# board.net
KiCad netlist of a schematic drawn in EAGLE
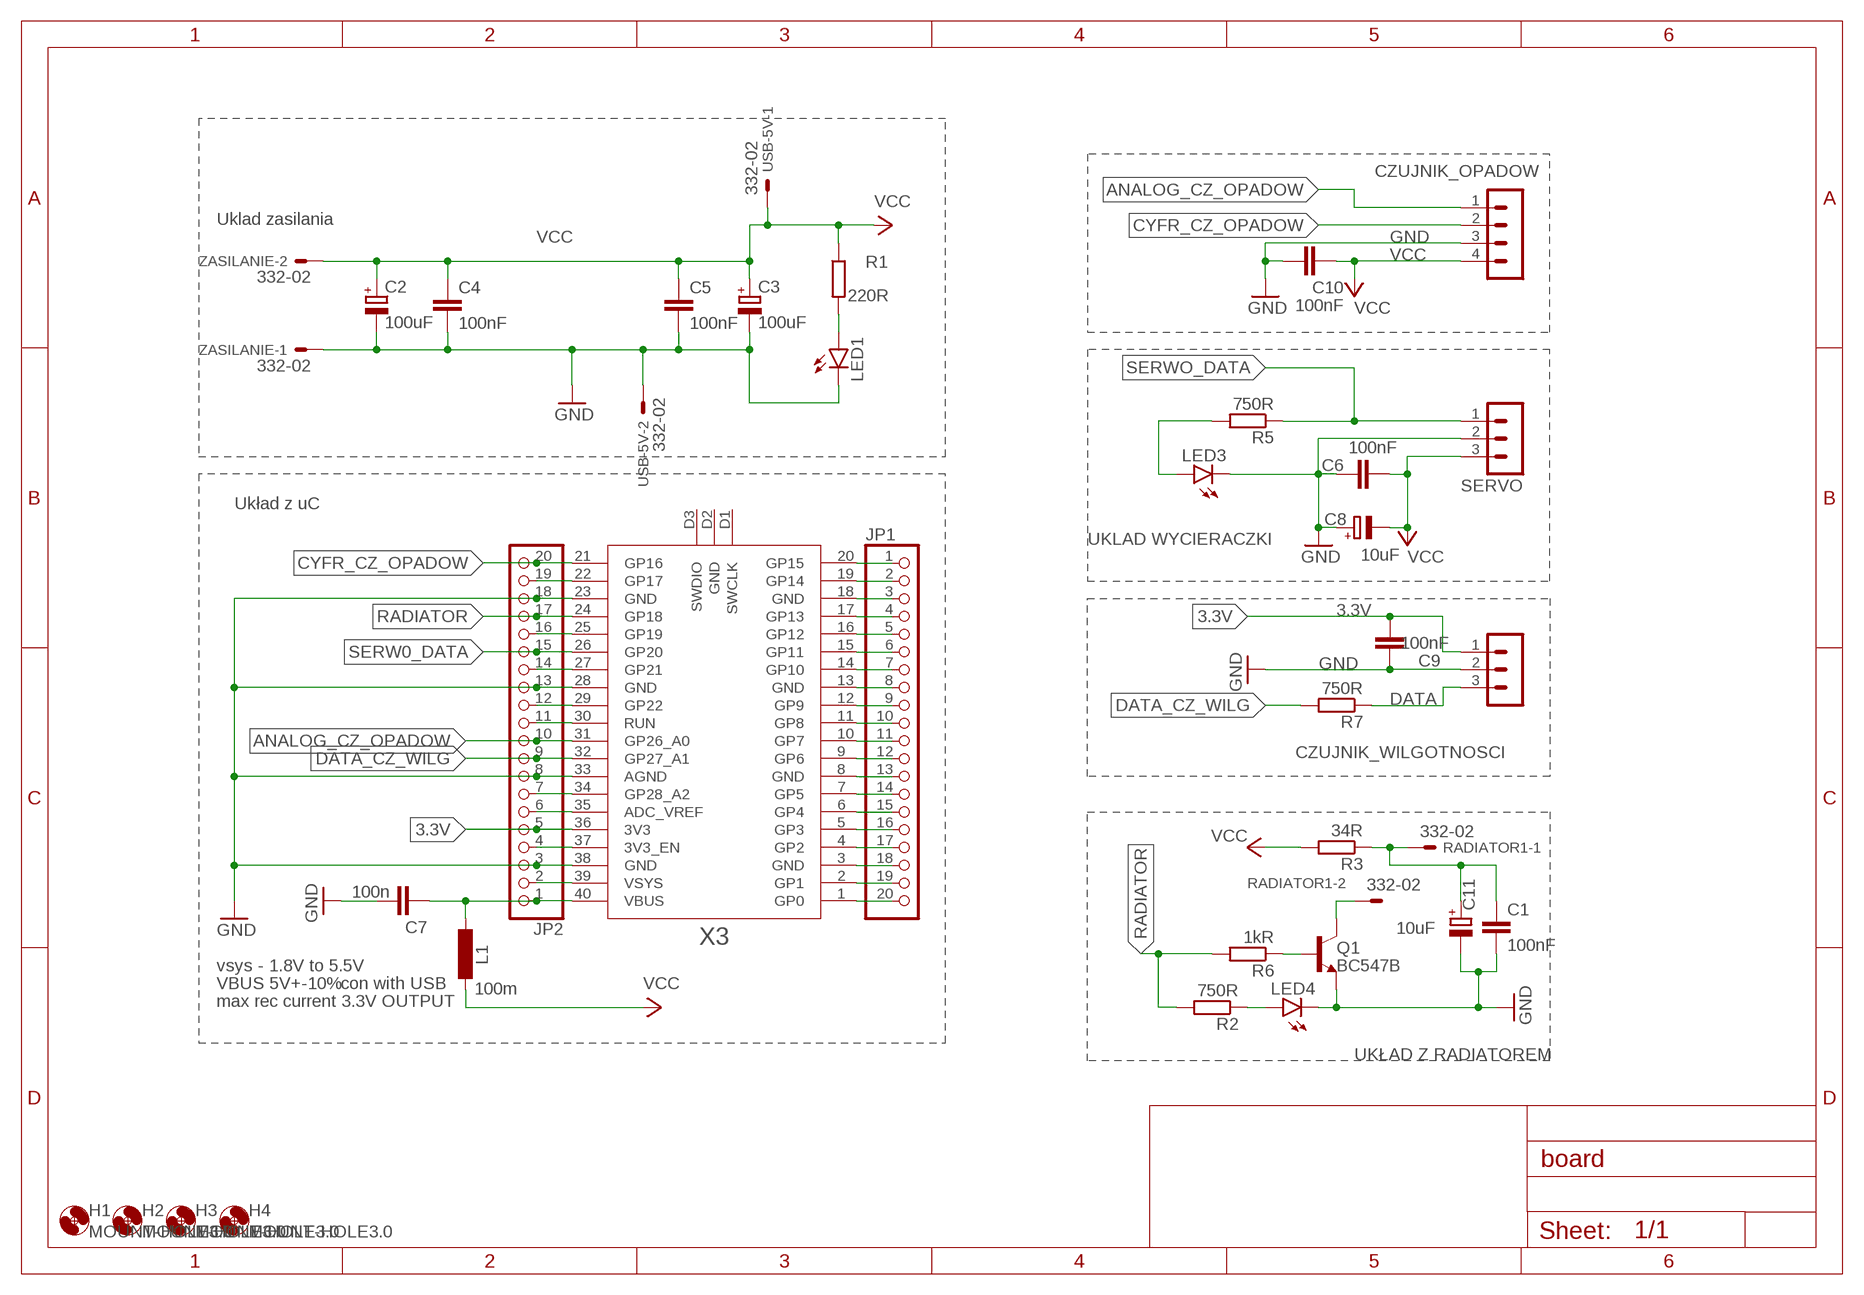
[diagram p0: schematic, sheet 1]

(export (version "E")
  (design (tool "Eeschema 10.0.6"))
  (components
    (comp (ref "C1")
      (value "100nF")
      (footprint "eagle-import:C0805")
      (libsource (lib "eagle-import") (part "C-EUC0805"))
    )
    (comp (ref "C2")
      (value "100uF")
      (footprint "eagle-import:UD-5X5,8_NICHICON")
      (libsource (lib "eagle-import") (part "CPOL-EUUD-5X5,8"))
    )
    (comp (ref "C3")
      (value "100uF")
      (footprint "eagle-import:UD-5X5,8_NICHICON")
      (libsource (lib "eagle-import") (part "CPOL-EUUD-5X5,8"))
    )
    (comp (ref "C4")
      (value "100nF")
      (footprint "eagle-import:C0805")
      (libsource (lib "eagle-import") (part "C-EUC0805"))
    )
    (comp (ref "C5")
      (value "100nF")
      (footprint "eagle-import:C0805")
      (libsource (lib "eagle-import") (part "C-EUC0805"))
    )
    (comp (ref "C6")
      (value "100nF")
      (footprint "eagle-import:C0805")
      (libsource (lib "eagle-import") (part "C-EUC0805"))
    )
    (comp (ref "C7")
      (value "100n")
      (footprint "eagle-import:C0603")
      (libsource (lib "eagle-import") (part "C-EUC0603"))
    )
    (comp (ref "C8")
      (value "10uF")
      (footprint "eagle-import:E5-8,5")
      (libsource (lib "eagle-import") (part "CPOL-EUE5-8.5"))
    )
    (comp (ref "C9")
      (value "100nF")
      (footprint "eagle-import:C0805")
      (libsource (lib "eagle-import") (part "C-EUC0805"))
    )
    (comp (ref "C10")
      (value "100nF")
      (footprint "eagle-import:C0805")
      (libsource (lib "eagle-import") (part "C-EUC0805"))
    )
    (comp (ref "C11")
      (value "10uF")
      (footprint "eagle-import:E5-8,5")
      (libsource (lib "eagle-import") (part "CPOL-EUE5-8.5"))
    )
    (comp (ref "CZUJNIK_OPADOW")
      (value "MA04-1")
      (footprint "eagle-import:MA04-1")
      (libsource (lib "eagle-import") (part "MA04-1"))
    )
    (comp (ref "CZUJNIK_WILGOTNOSCI")
      (value "MA03-1")
      (footprint "eagle-import:MA03-1")
      (libsource (lib "eagle-import") (part "MA03-1"))
    )
    (comp (ref "H1")
      (value "MOUNT-HOLE3.0")
      (footprint "eagle-import:3,0")
      (libsource (lib "eagle-import") (part "MOUNT-HOLE3.0"))
    )
    (comp (ref "H2")
      (value "MOUNT-HOLE3.0")
      (footprint "eagle-import:3,0")
      (libsource (lib "eagle-import") (part "MOUNT-HOLE3.0"))
    )
    (comp (ref "H3")
      (value "MOUNT-HOLE3.0")
      (footprint "eagle-import:3,0")
      (libsource (lib "eagle-import") (part "MOUNT-HOLE3.0"))
    )
    (comp (ref "H4")
      (value "MOUNT-HOLE3.0")
      (footprint "eagle-import:3,0")
      (libsource (lib "eagle-import") (part "MOUNT-HOLE3.0"))
    )
    (comp (ref "JP1")
      (value "PINHD-1X20")
      (footprint "eagle-import:1X20")
      (libsource (lib "eagle-import") (part "PINHD-1X20"))
    )
    (comp (ref "JP2")
      (value "PINHD-1X20")
      (footprint "eagle-import:1X20")
      (libsource (lib "eagle-import") (part "PINHD-1X20"))
    )
    (comp (ref "L1")
      (value "100m")
      (footprint "eagle-import:L2012C")
      (libsource (lib "eagle-import") (part "L-EUL2012C"))
    )
    (comp (ref "LED1")
      (value "LEDSML0805")
      (footprint "eagle-import:SML0805")
      (libsource (lib "eagle-import") (part "LEDSML0805"))
    )
    (comp (ref "LED3")
      (value "LEDSML0805")
      (footprint "eagle-import:SML0805")
      (libsource (lib "eagle-import") (part "LEDSML0805"))
    )
    (comp (ref "LED4")
      (value "LEDSML0805")
      (footprint "eagle-import:SML0805")
      (libsource (lib "eagle-import") (part "LEDSML0805"))
    )
    (comp (ref "Q1")
      (value "BC547B")
      (footprint "eagle-import:TO92")
      (libsource (lib "eagle-import") (part "BC547B"))
    )
    (comp (ref "R1")
      (value "220R")
      (footprint "eagle-import:R0805")
      (libsource (lib "eagle-import") (part "R-EU_R0805"))
    )
    (comp (ref "R2")
      (value "750R")
      (footprint "eagle-import:R0805")
      (libsource (lib "eagle-import") (part "R-EU_R0805"))
    )
    (comp (ref "R3")
      (value "34R")
      (footprint "eagle-import:R0805")
      (libsource (lib "eagle-import") (part "R-EU_R0805"))
    )
    (comp (ref "R5")
      (value "750R")
      (footprint "eagle-import:R0805")
      (libsource (lib "eagle-import") (part "R-EU_R0805"))
    )
    (comp (ref "R6")
      (value "1kR")
      (footprint "eagle-import:R0805")
      (libsource (lib "eagle-import") (part "R-EU_R0805"))
    )
    (comp (ref "R7")
      (value "750R")
      (footprint "eagle-import:R0805")
      (libsource (lib "eagle-import") (part "R-EU_R0805"))
    )
    (comp (ref "RADIATOR1")
      (value "332-02")
      (footprint "eagle-import:332-02")
      (libsource (lib "eagle-import") (part "332-02"))
    )
    (comp (ref "SERVO")
      (value "MA03-1")
      (footprint "eagle-import:MA03-1")
      (libsource (lib "eagle-import") (part "MA03-1"))
    )
    (comp (ref "USB-5V")
      (value "332-02")
      (footprint "eagle-import:332-02")
      (libsource (lib "eagle-import") (part "332-02"))
    )
    (comp (ref "X3")
      (value "RPI_PICO_IG-TH")
      (footprint "eagle-import:RPI_PICO_TH")
      (libsource (lib "eagle-import") (part "RPI_PICO_IG-TH"))
    )
    (comp (ref "ZASILANIE")
      (value "332-02")
      (footprint "eagle-import:332-02")
      (libsource (lib "eagle-import") (part "332-02"))
    )
  )
  (nets
    (net (code "1") (name "/DATA") (class "Default")
      (node (ref "CZUJNIK_WILGOTNOSCI") (pin "3") (pinfunction "3_3") (pintype "passive"))
      (node (ref "R7") (pin "1") (pinfunction "1_1") (pintype "passive"))
    )
    (net (code "2") (name "3.3V") (class "Default")
      (node (ref "C9") (pin "2") (pinfunction "2_2") (pintype "passive"))
      (node (ref "CZUJNIK_WILGOTNOSCI") (pin "1") (pinfunction "1_1") (pintype "passive"))
      (node (ref "JP2") (pin "5") (pinfunction "5_5") (pintype "passive"))
      (node (ref "X3") (pin "36") (pinfunction "3V3_36") (pintype "bidirectional"))
    )
    (net (code "3") (name "ANALOG_CZ_OPADOW") (class "Default")
      (node (ref "CZUJNIK_OPADOW") (pin "1") (pinfunction "1_1") (pintype "passive"))
      (node (ref "JP2") (pin "10") (pinfunction "10_10") (pintype "passive"))
      (node (ref "X3") (pin "31") (pinfunction "GP26_A0_31") (pintype "bidirectional"))
    )
    (net (code "4") (name "CYFR_CZ_OPADOW") (class "Default")
      (node (ref "CZUJNIK_OPADOW") (pin "2") (pinfunction "2_2") (pintype "passive"))
      (node (ref "JP2") (pin "20") (pinfunction "20_20") (pintype "passive"))
      (node (ref "X3") (pin "21") (pinfunction "GP16_21") (pintype "bidirectional"))
    )
    (net (code "5") (name "DATA_CZ_WILG") (class "Default")
      (node (ref "JP2") (pin "9") (pinfunction "9_9") (pintype "passive"))
      (node (ref "R7") (pin "2") (pinfunction "2_2") (pintype "passive"))
      (node (ref "X3") (pin "32") (pinfunction "GP27_A1_32") (pintype "bidirectional"))
    )
    (net (code "6") (name "GND") (class "Default")
      (node (ref "C1") (pin "2") (pinfunction "2_2") (pintype "passive"))
      (node (ref "C10") (pin "2") (pinfunction "2_2") (pintype "passive"))
      (node (ref "C11") (pin "-") (pinfunction "-_-") (pintype "passive"))
      (node (ref "C2") (pin "-") (pinfunction "-_-") (pintype "passive"))
      (node (ref "C3") (pin "-") (pinfunction "-_-") (pintype "passive"))
      (node (ref "C4") (pin "2") (pinfunction "2_2") (pintype "passive"))
      (node (ref "C5") (pin "2") (pinfunction "2_2") (pintype "passive"))
      (node (ref "C6") (pin "1") (pinfunction "1_1") (pintype "passive"))
      (node (ref "C7") (pin "2") (pinfunction "2_2") (pintype "passive"))
      (node (ref "C8") (pin "+") (pinfunction "+_+") (pintype "passive"))
      (node (ref "C9") (pin "1") (pinfunction "1_1") (pintype "passive"))
      (node (ref "CZUJNIK_OPADOW") (pin "3") (pinfunction "3_3") (pintype "passive"))
      (node (ref "CZUJNIK_WILGOTNOSCI") (pin "2") (pinfunction "2_2") (pintype "passive"))
      (node (ref "JP2") (pin "13") (pinfunction "13_13") (pintype "passive"))
      (node (ref "JP2") (pin "18") (pinfunction "18_18") (pintype "passive"))
      (node (ref "JP2") (pin "3") (pinfunction "3_3") (pintype "passive"))
      (node (ref "JP2") (pin "8") (pinfunction "8_8") (pintype "passive"))
      (node (ref "LED1") (pin "C") (pinfunction "C_C") (pintype "passive"))
      (node (ref "LED3") (pin "C") (pinfunction "C_C") (pintype "passive"))
      (node (ref "LED4") (pin "C") (pinfunction "C_C") (pintype "passive"))
      (node (ref "Q1") (pin "1") (pinfunction "E_1") (pintype "passive"))
      (node (ref "SERVO") (pin "2") (pinfunction "2_2") (pintype "passive"))
      (node (ref "USB-5V") (pin "2") (pinfunction "S_2") (pintype "passive"))
      (node (ref "X3") (pin "23") (pinfunction "GND_23") (pintype "bidirectional"))
      (node (ref "X3") (pin "28") (pinfunction "GND_28") (pintype "bidirectional"))
      (node (ref "X3") (pin "33") (pinfunction "AGND_33") (pintype "bidirectional"))
      (node (ref "X3") (pin "38") (pinfunction "GND_38") (pintype "bidirectional"))
      (node (ref "ZASILANIE") (pin "1") (pinfunction "S_1") (pintype "passive"))
    )
    (net (code "7") (name "Net-(JP1-Pad3)") (class "Default")
      (node (ref "JP1") (pin "3") (pinfunction "3_3") (pintype "passive"))
      (node (ref "X3") (pin "18") (pinfunction "GND_18") (pintype "bidirectional"))
    )
    (net (code "8") (name "Net-(JP1-Pad8)") (class "Default")
      (node (ref "JP1") (pin "8") (pinfunction "8_8") (pintype "passive"))
      (node (ref "X3") (pin "13") (pinfunction "GND_13") (pintype "bidirectional"))
    )
    (net (code "9") (name "Net-(JP1-Pad13)") (class "Default")
      (node (ref "JP1") (pin "13") (pinfunction "13_13") (pintype "passive"))
      (node (ref "X3") (pin "8") (pinfunction "GND_8") (pintype "bidirectional"))
    )
    (net (code "10") (name "Net-(JP1-Pad18)") (class "Default")
      (node (ref "JP1") (pin "18") (pinfunction "18_18") (pintype "passive"))
      (node (ref "X3") (pin "3") (pinfunction "GND_3") (pintype "bidirectional"))
    )
    (net (code "11") (name "Net-(LED1-PadA)") (class "Default")
      (node (ref "LED1") (pin "A") (pinfunction "A_A") (pintype "passive"))
      (node (ref "R1") (pin "2") (pinfunction "2_2") (pintype "passive"))
    )
    (net (code "12") (name "Net-(LED3-PadA)") (class "Default")
      (node (ref "LED3") (pin "A") (pinfunction "A_A") (pintype "passive"))
      (node (ref "R5") (pin "2") (pinfunction "2_2") (pintype "passive"))
    )
    (net (code "13") (name "Net-(LED4-PadA)") (class "Default")
      (node (ref "LED4") (pin "A") (pinfunction "A_A") (pintype "passive"))
      (node (ref "R2") (pin "1") (pinfunction "1_1") (pintype "passive"))
    )
    (net (code "14") (name "Net-(Q1-B)") (class "Default")
      (node (ref "Q1") (pin "2") (pinfunction "B_2") (pintype "passive"))
      (node (ref "R6") (pin "1") (pinfunction "1_1") (pintype "passive"))
    )
    (net (code "15") (name "Net-(Q1-C)") (class "Default")
      (node (ref "Q1") (pin "3") (pinfunction "C_3") (pintype "passive"))
      (node (ref "RADIATOR1") (pin "2") (pinfunction "S_2") (pintype "passive"))
    )
    (net (code "16") (name "Net-(RADIATOR1A-S)") (class "Default")
      (node (ref "C1") (pin "1") (pinfunction "1_1") (pintype "passive"))
      (node (ref "C11") (pin "+") (pinfunction "+_+") (pintype "passive"))
      (node (ref "R3") (pin "1") (pinfunction "1_1") (pintype "passive"))
      (node (ref "RADIATOR1") (pin "1") (pinfunction "S_1") (pintype "passive"))
    )
    (net (code "17") (name "Net-(X3-3V3_EN)") (class "Default")
      (node (ref "JP2") (pin "4") (pinfunction "4_4") (pintype "passive"))
      (node (ref "X3") (pin "37") (pinfunction "3V3_EN_37") (pintype "bidirectional"))
    )
    (net (code "18") (name "Net-(X3-ADC_VREF)") (class "Default")
      (node (ref "JP2") (pin "6") (pinfunction "6_6") (pintype "passive"))
      (node (ref "X3") (pin "35") (pinfunction "ADC_VREF_35") (pintype "bidirectional"))
    )
    (net (code "19") (name "Net-(X3-GP0)") (class "Default")
      (node (ref "JP1") (pin "20") (pinfunction "20_20") (pintype "passive"))
      (node (ref "X3") (pin "1") (pinfunction "GP0_1") (pintype "bidirectional"))
    )
    (net (code "20") (name "Net-(X3-GP1)") (class "Default")
      (node (ref "JP1") (pin "19") (pinfunction "19_19") (pintype "passive"))
      (node (ref "X3") (pin "2") (pinfunction "GP1_2") (pintype "bidirectional"))
    )
    (net (code "21") (name "Net-(X3-GP2)") (class "Default")
      (node (ref "JP1") (pin "17") (pinfunction "17_17") (pintype "passive"))
      (node (ref "X3") (pin "4") (pinfunction "GP2_4") (pintype "bidirectional"))
    )
    (net (code "22") (name "Net-(X3-GP3)") (class "Default")
      (node (ref "JP1") (pin "16") (pinfunction "16_16") (pintype "passive"))
      (node (ref "X3") (pin "5") (pinfunction "GP3_5") (pintype "bidirectional"))
    )
    (net (code "23") (name "Net-(X3-GP4)") (class "Default")
      (node (ref "JP1") (pin "15") (pinfunction "15_15") (pintype "passive"))
      (node (ref "X3") (pin "6") (pinfunction "GP4_6") (pintype "bidirectional"))
    )
    (net (code "24") (name "Net-(X3-GP5)") (class "Default")
      (node (ref "JP1") (pin "14") (pinfunction "14_14") (pintype "passive"))
      (node (ref "X3") (pin "7") (pinfunction "GP5_7") (pintype "bidirectional"))
    )
    (net (code "25") (name "Net-(X3-GP6)") (class "Default")
      (node (ref "JP1") (pin "12") (pinfunction "12_12") (pintype "passive"))
      (node (ref "X3") (pin "9") (pinfunction "GP6_9") (pintype "bidirectional"))
    )
    (net (code "26") (name "Net-(X3-GP7)") (class "Default")
      (node (ref "JP1") (pin "11") (pinfunction "11_11") (pintype "passive"))
      (node (ref "X3") (pin "10") (pinfunction "GP7_10") (pintype "bidirectional"))
    )
    (net (code "27") (name "Net-(X3-GP8)") (class "Default")
      (node (ref "JP1") (pin "10") (pinfunction "10_10") (pintype "passive"))
      (node (ref "X3") (pin "11") (pinfunction "GP8_11") (pintype "bidirectional"))
    )
    (net (code "28") (name "Net-(X3-GP9)") (class "Default")
      (node (ref "JP1") (pin "9") (pinfunction "9_9") (pintype "passive"))
      (node (ref "X3") (pin "12") (pinfunction "GP9_12") (pintype "bidirectional"))
    )
    (net (code "29") (name "Net-(X3-GP10)") (class "Default")
      (node (ref "JP1") (pin "7") (pinfunction "7_7") (pintype "passive"))
      (node (ref "X3") (pin "14") (pinfunction "GP10_14") (pintype "bidirectional"))
    )
    (net (code "30") (name "Net-(X3-GP11)") (class "Default")
      (node (ref "JP1") (pin "6") (pinfunction "6_6") (pintype "passive"))
      (node (ref "X3") (pin "15") (pinfunction "GP11_15") (pintype "bidirectional"))
    )
    (net (code "31") (name "Net-(X3-GP12)") (class "Default")
      (node (ref "JP1") (pin "5") (pinfunction "5_5") (pintype "passive"))
      (node (ref "X3") (pin "16") (pinfunction "GP12_16") (pintype "bidirectional"))
    )
    (net (code "32") (name "Net-(X3-GP13)") (class "Default")
      (node (ref "JP1") (pin "4") (pinfunction "4_4") (pintype "passive"))
      (node (ref "X3") (pin "17") (pinfunction "GP13_17") (pintype "bidirectional"))
    )
    (net (code "33") (name "Net-(X3-GP14)") (class "Default")
      (node (ref "JP1") (pin "2") (pinfunction "2_2") (pintype "passive"))
      (node (ref "X3") (pin "19") (pinfunction "GP14_19") (pintype "bidirectional"))
    )
    (net (code "34") (name "Net-(X3-GP15)") (class "Default")
      (node (ref "JP1") (pin "1") (pinfunction "1_1") (pintype "passive"))
      (node (ref "X3") (pin "20") (pinfunction "GP15_20") (pintype "bidirectional"))
    )
    (net (code "35") (name "Net-(X3-GP17)") (class "Default")
      (node (ref "JP2") (pin "19") (pinfunction "19_19") (pintype "passive"))
      (node (ref "X3") (pin "22") (pinfunction "GP17_22") (pintype "bidirectional"))
    )
    (net (code "36") (name "Net-(X3-GP19)") (class "Default")
      (node (ref "JP2") (pin "16") (pinfunction "16_16") (pintype "passive"))
      (node (ref "X3") (pin "25") (pinfunction "GP19_25") (pintype "bidirectional"))
    )
    (net (code "37") (name "Net-(X3-GP21)") (class "Default")
      (node (ref "JP2") (pin "14") (pinfunction "14_14") (pintype "passive"))
      (node (ref "X3") (pin "27") (pinfunction "GP21_27") (pintype "bidirectional"))
    )
    (net (code "38") (name "Net-(X3-GP22)") (class "Default")
      (node (ref "JP2") (pin "12") (pinfunction "12_12") (pintype "passive"))
      (node (ref "X3") (pin "29") (pinfunction "GP22_29") (pintype "bidirectional"))
    )
    (net (code "39") (name "Net-(X3-GP28_A2)") (class "Default")
      (node (ref "JP2") (pin "7") (pinfunction "7_7") (pintype "passive"))
      (node (ref "X3") (pin "34") (pinfunction "GP28_A2_34") (pintype "bidirectional"))
    )
    (net (code "40") (name "Net-(X3-RUN)") (class "Default")
      (node (ref "JP2") (pin "11") (pinfunction "11_11") (pintype "passive"))
      (node (ref "X3") (pin "30") (pinfunction "RUN_30") (pintype "bidirectional"))
    )
    (net (code "41") (name "Net-(X3-VBUS)") (class "Default")
      (node (ref "C7") (pin "1") (pinfunction "1_1") (pintype "passive"))
      (node (ref "JP2") (pin "1") (pinfunction "1_1") (pintype "passive"))
      (node (ref "L1") (pin "2") (pinfunction "2_2") (pintype "passive"))
      (node (ref "X3") (pin "40") (pinfunction "VBUS_40") (pintype "bidirectional"))
    )
    (net (code "42") (name "Net-(X3-VSYS)") (class "Default")
      (node (ref "JP2") (pin "2") (pinfunction "2_2") (pintype "passive"))
      (node (ref "X3") (pin "39") (pinfunction "VSYS_39") (pintype "bidirectional"))
    )
    (net (code "43") (name "RADIATOR") (class "Default")
      (node (ref "JP2") (pin "17") (pinfunction "17_17") (pintype "passive"))
      (node (ref "R2") (pin "2") (pinfunction "2_2") (pintype "passive"))
      (node (ref "R6") (pin "2") (pinfunction "2_2") (pintype "passive"))
      (node (ref "X3") (pin "24") (pinfunction "GP18_24") (pintype "bidirectional"))
    )
    (net (code "44") (name "SERW0_DATA") (class "Default")
      (node (ref "JP2") (pin "15") (pinfunction "15_15") (pintype "passive"))
      (node (ref "X3") (pin "26") (pinfunction "GP20_26") (pintype "bidirectional"))
    )
    (net (code "45") (name "SERWO_DATA") (class "Default")
      (node (ref "R5") (pin "1") (pinfunction "1_1") (pintype "passive"))
      (node (ref "SERVO") (pin "1") (pinfunction "1_1") (pintype "passive"))
    )
    (net (code "46") (name "VCC") (class "Default")
      (node (ref "C10") (pin "1") (pinfunction "1_1") (pintype "passive"))
      (node (ref "C2") (pin "+") (pinfunction "+_+") (pintype "passive"))
      (node (ref "C3") (pin "+") (pinfunction "+_+") (pintype "passive"))
      (node (ref "C4") (pin "1") (pinfunction "1_1") (pintype "passive"))
      (node (ref "C5") (pin "1") (pinfunction "1_1") (pintype "passive"))
      (node (ref "C6") (pin "2") (pinfunction "2_2") (pintype "passive"))
      (node (ref "C8") (pin "-") (pinfunction "-_-") (pintype "passive"))
      (node (ref "CZUJNIK_OPADOW") (pin "4") (pinfunction "4_4") (pintype "passive"))
      (node (ref "L1") (pin "1") (pinfunction "1_1") (pintype "passive"))
      (node (ref "R1") (pin "1") (pinfunction "1_1") (pintype "passive"))
      (node (ref "R3") (pin "2") (pinfunction "2_2") (pintype "passive"))
      (node (ref "SERVO") (pin "3") (pinfunction "3_3") (pintype "passive"))
      (node (ref "USB-5V") (pin "1") (pinfunction "S_1") (pintype "passive"))
      (node (ref "ZASILANIE") (pin "2") (pinfunction "S_2") (pintype "passive"))
    )
    (net (code "47") (name "unconnected-(X3-GND-PadD2)") (class "Default")
      (node (ref "X3") (pin "D2") (pinfunction "GND_D2") (pintype "bidirectional"))
    )
    (net (code "48") (name "unconnected-(X3-SWCLK-PadD1)") (class "Default")
      (node (ref "X3") (pin "D1") (pinfunction "SWCLK_D1") (pintype "bidirectional"))
    )
    (net (code "49") (name "unconnected-(X3-SWDIO-PadD3)") (class "Default")
      (node (ref "X3") (pin "D3") (pinfunction "SWDIO_D3") (pintype "bidirectional"))
    )
  )
)
